# design.net
KiCad netlist of a schematic drawn in Altium Designer
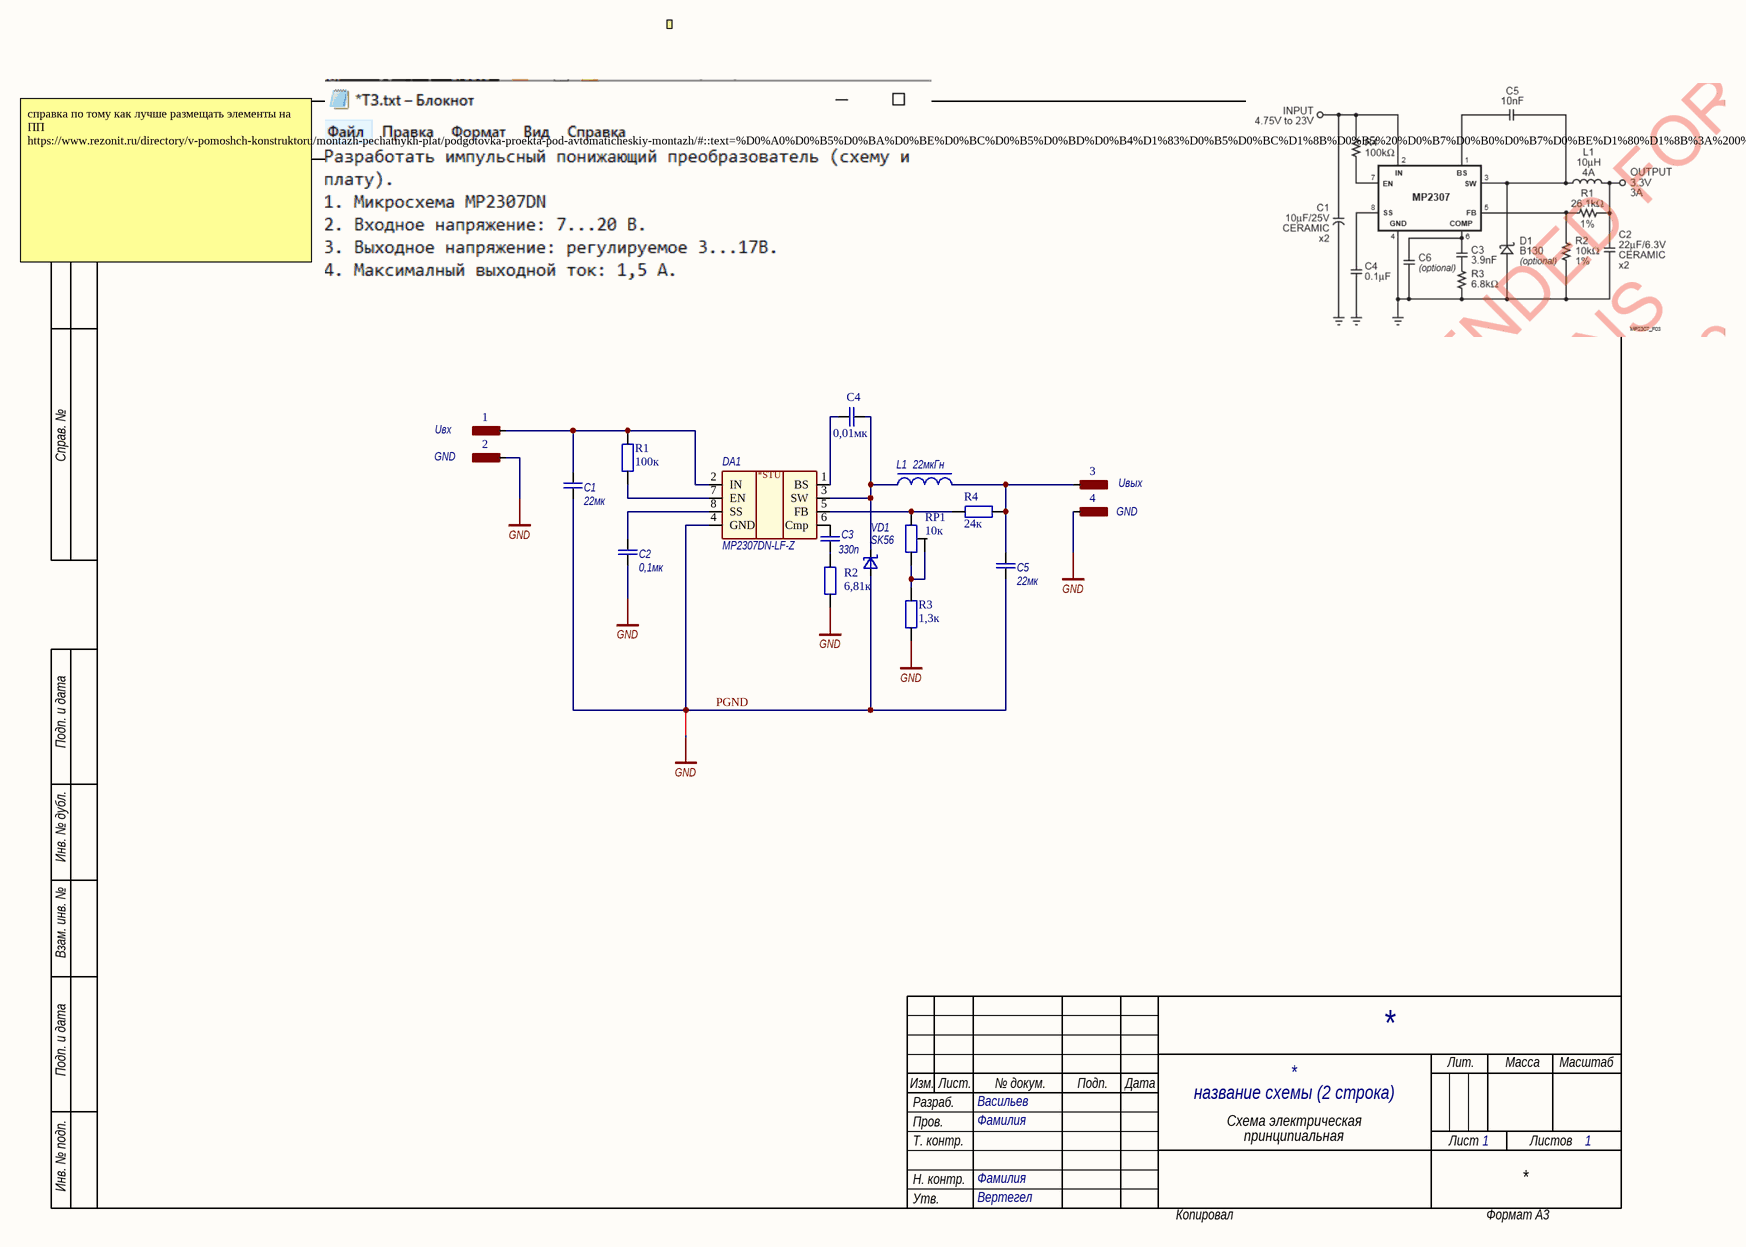
[diagram p0: Схема преобразователя.SchDoc]

(export (version "E")
  (design (tool "Eeschema 10.0.6"))
  (components
    (comp (ref "1")
      (value "Контактная площадка")
      (footprint "Cont_point")
      (description "Контактная площадка на плате, 1,3х2 мм")
      (libsource (lib "RSGU_LIB") (part "Cont_point"))
    )
    (comp (ref "2")
      (value "Контактная площадка")
      (footprint "Cont_point")
      (description "Контактная площадка на плате, 1,3х2 мм")
      (libsource (lib "RSGU_LIB") (part "Cont_point"))
    )
    (comp (ref "3")
      (value "Контактная площадка")
      (footprint "Cont_point")
      (description "Контактная площадка на плате, 1,3х2 мм")
      (libsource (lib "") (part "Cont_point_1"))
    )
    (comp (ref "4")
      (value "Контактная площадка")
      (footprint "Cont_point")
      (description "Контактная площадка на плате, 1,3х2 мм")
      (libsource (lib "") (part "Cont_point_1"))
    )
    (comp (ref "BR1")
      (value "Соединение цепей")
      (footprint "BREAK_GND")
      (description "Соединение разных типов земли или питания")
      (libsource (lib "RSGU_LIB") (part "GND-break"))
    )
    (comp (ref "C1")
      (value "22мк")
      (footprint "C0805")
      (description "0805, 22мк, ±20%, 25В, X5R")
      (fields (field (name "TOLERANCE") "±20%") (field (name "MANUFACTURERPARTNUMBER") "CC0805MKX5R5BB476"))
      (libsource (lib "RSGU_LIB") (part "Cap_NP"))
    )
    (comp (ref "C2")
      (value "0,1мк")
      (footprint "C0603")
      (description "0603, 0,1мк, ±10%, 50В, X7R")
      (fields
        (field (name "TOLERANCE") "±10%")
        (field (name "MANUFACTURERPARTNUMBER") "CGA3E2X7R1H104K080AA")
      )
      (libsource (lib "RSGU_LIB") (part "Cap_NP"))
    )
    (comp (ref "C3")
      (value "330п")
      (footprint "C0603")
      (description "0603, 1мк, ±20%, 16В, X7R Automotive")
      (fields (field (name "TOLERANCE") "±20%") (field (name "MANUFACTURERPARTNUMBER") "GCM188R71C105MA64"))
      (libsource (lib "RSGU_LIB") (part "Cap_NP"))
    )
    (comp (ref "C4")
      (value "0,01мк")
      (footprint "C0603")
      (description "0603, 0,01мк, ±10%, 50В, X7R")
      (fields (field (name "TOLERANCE") "±10%") (field (name "MANUFACTURERPARTNUMBER") "GRM188R71H103KA01"))
      (libsource (lib "RSGU_LIB") (part "Cap_NP"))
    )
    (comp (ref "C5")
      (value "22мк")
      (footprint "C0805")
      (description "0805, 22мк, ±20%, 25В, X5R")
      (fields (field (name "TOLERANCE") "±20%") (field (name "MANUFACTURERPARTNUMBER") "CC0805MKX5R5BB476"))
      (libsource (lib "RSGU_LIB") (part "Cap_NP"))
    )
    (comp (ref "DA1")
      (value "Микросхема MP2307DN-LF-Z")
      (footprint "SO8_PowerPad")
      (description "DC/DC пониж. преобр., Вх(4,75-23В), вых - 3А, 340 кГц, SMD. NRFND!!!")
      (fields (field (name "MANUFACTURERPARTNUMBER") "MP2307DN-LF-Z") (field (name "MANUFACTURER") "MPS"))
      (libsource (lib "RSGU_LIB") (part "MP2307"))
    )
    (comp (ref "L1")
      (value "22мкГн")
      (footprint "VLS6045")
      (description "Дроссель 22мкГн, корпус - VLS6045")
      (fields (field (name "TOLERANCE") "±20%") (field (name "MANUFACTURERPARTNUMBER") "VLS6045EX-220M"))
      (libsource (lib "RSGU_LIB") (part "Ind_ferrit"))
    )
    (comp (ref "R1")
      (value "100к")
      (footprint "R0603")
      (description "Общего применения, 5%")
      (fields (field (name "TOLERANCE") "±5%") (field (name "MANUFACTURERPARTNUMBER") "Р1-12-0,1-100 кОм±5%"))
      (libsource (lib "RSGU_LIB") (part "Res"))
    )
    (comp (ref "R2")
      (value "6,81к")
      (footprint "R0603")
      (description "Общего применения, 1%")
      (fields
        (field (name "TOLERANCE") "±1%")
        (field (name "MANUFACTURERPARTNUMBER") "Р1-8В-0,1-6,81 кОм±1%-Т-А-М")
      )
      (libsource (lib "RSGU_LIB") (part "Res"))
    )
    (comp (ref "R3")
      (value "1,3к")
      (footprint "R0603")
      (description "Общего применения, 5%")
      (fields (field (name "TOLERANCE") "±5%") (field (name "MANUFACTURERPARTNUMBER") "Р1-12-0,1-1,2 кОм±5%"))
      (libsource (lib "RSGU_LIB") (part "Res"))
    )
    (comp (ref "R4")
      (value "24к")
      (footprint "R0603")
      (description "Общего применения, 5%")
      (fields
        (field (name "TOLERANCE") "±5%")
        (field (name "MANUFACTURERPARTNUMBER") "Р1-8В-0,1-24 кОм±5%-Т-А-М")
      )
      (libsource (lib "RSGU_LIB") (part "Res"))
    )
    (comp (ref "RP1")
      (value "10к")
      (footprint "3296W")
      (description "Резистор подстроечный многооборотный 10к 0.5Вт Bourns")
      (fields (field (name "TOLERANCE") "±20%") (field (name "MANUFACTURERPARTNUMBER") "3296W-1-202LF"))
      (libsource (lib "RSGU_LIB") (part "Res_ADJ_123"))
    )
    (comp (ref "VD1")
      (value "Диод Шоттки SK56")
      (footprint "DO214Aa")
      (description "Диод Шоттки SK56 (SMD, 60В / 5А)")
      (fields
        (field (name "MANUFACTURERPARTNUMBER") "SK56")
        (field (name "MANUFACTURER") "Diotec Semiconductor")
      )
      (libsource (lib "RSGU_LIB") (part "Diode_Shottky"))
    )
  )
  (nets
    (net (code "1") (name "/PGND") (class "Default")
      (node (ref "BR1") (pin "2") (pinfunction "2_2") (pintype "passive"))
      (node (ref "C1") (pin "2") (pinfunction "2_2") (pintype "passive"))
      (node (ref "C5") (pin "2") (pinfunction "2_2") (pintype "passive"))
      (node (ref "DA1") (pin "4") (pinfunction "GND_4") (pintype "power_in"))
      (node (ref "VD1") (pin "1") (pinfunction "Анод_1") (pintype "passive"))
    )
    (net (code "2") (name "GND") (class "Default")
      (node (ref "2") (pin "1") (pinfunction "1_1") (pintype "passive"))
      (node (ref "4") (pin "1") (pinfunction "1_1") (pintype "passive"))
      (node (ref "BR1") (pin "1") (pinfunction "1_1") (pintype "passive"))
      (node (ref "C2") (pin "2") (pinfunction "2_2") (pintype "passive"))
      (node (ref "R2") (pin "2") (pinfunction "2_2") (pintype "passive"))
      (node (ref "R3") (pin "2") (pinfunction "2_2") (pintype "passive"))
    )
    (net (code "3") (name "Net-(3-Pad1)") (class "Default")
      (node (ref "3") (pin "1") (pinfunction "1_1") (pintype "passive"))
      (node (ref "C5") (pin "1") (pinfunction "1_1") (pintype "passive"))
      (node (ref "L1") (pin "1") (pinfunction "1_1") (pintype "passive"))
      (node (ref "R4") (pin "2") (pinfunction "2_2") (pintype "passive"))
    )
    (net (code "4") (name "Net-(C3-Pad2)") (class "Default")
      (node (ref "C3") (pin "2") (pinfunction "2_2") (pintype "passive"))
      (node (ref "R2") (pin "1") (pinfunction "1_1") (pintype "passive"))
    )
    (net (code "5") (name "Net-(DA1-BS)") (class "Default")
      (node (ref "C4") (pin "1") (pinfunction "1_1") (pintype "passive"))
      (node (ref "DA1") (pin "1") (pinfunction "BS_1") (pintype "passive"))
    )
    (net (code "6") (name "Net-(DA1-Cmp)") (class "Default")
      (node (ref "C3") (pin "1") (pinfunction "1_1") (pintype "passive"))
      (node (ref "DA1") (pin "6") (pinfunction "Cmp_6") (pintype "passive"))
    )
    (net (code "7") (name "Net-(DA1-EN)") (class "Default")
      (node (ref "DA1") (pin "7") (pinfunction "EN_7") (pintype "passive"))
      (node (ref "R1") (pin "2") (pinfunction "2_2") (pintype "passive"))
    )
    (net (code "8") (name "Net-(DA1-FB)") (class "Default")
      (node (ref "DA1") (pin "5") (pinfunction "FB_5") (pintype "passive"))
      (node (ref "R4") (pin "1") (pinfunction "1_1") (pintype "passive"))
      (node (ref "RP1") (pin "3") (pinfunction "3_3") (pintype "passive"))
    )
    (net (code "9") (name "Net-(DA1-IN)") (class "Default")
      (node (ref "1") (pin "1") (pinfunction "1_1") (pintype "passive"))
      (node (ref "C1") (pin "1") (pinfunction "1_1") (pintype "passive"))
      (node (ref "DA1") (pin "2") (pinfunction "IN_2") (pintype "power_in"))
      (node (ref "R1") (pin "1") (pinfunction "1_1") (pintype "passive"))
    )
    (net (code "10") (name "Net-(DA1-SS)") (class "Default")
      (node (ref "C2") (pin "1") (pinfunction "1_1") (pintype "passive"))
      (node (ref "DA1") (pin "8") (pinfunction "SS_8") (pintype "passive"))
    )
    (net (code "11") (name "Net-(DA1-SW)") (class "Default")
      (node (ref "C4") (pin "2") (pinfunction "2_2") (pintype "passive"))
      (node (ref "DA1") (pin "3") (pinfunction "SW_3") (pintype "passive"))
      (node (ref "L1") (pin "2") (pinfunction "2_2") (pintype "passive"))
      (node (ref "VD1") (pin "2") (pinfunction "Катод_2") (pintype "passive"))
    )
    (net (code "12") (name "Net-(R3-Pad1)") (class "Default")
      (node (ref "R3") (pin "1") (pinfunction "1_1") (pintype "passive"))
      (node (ref "RP1") (pin "1") (pinfunction "1_1") (pintype "passive"))
      (node (ref "RP1") (pin "2") (pinfunction "2_2") (pintype "passive"))
    )
  )
)
